# keyboard84.net
KiCad netlist of a schematic drawn in Altium Designer
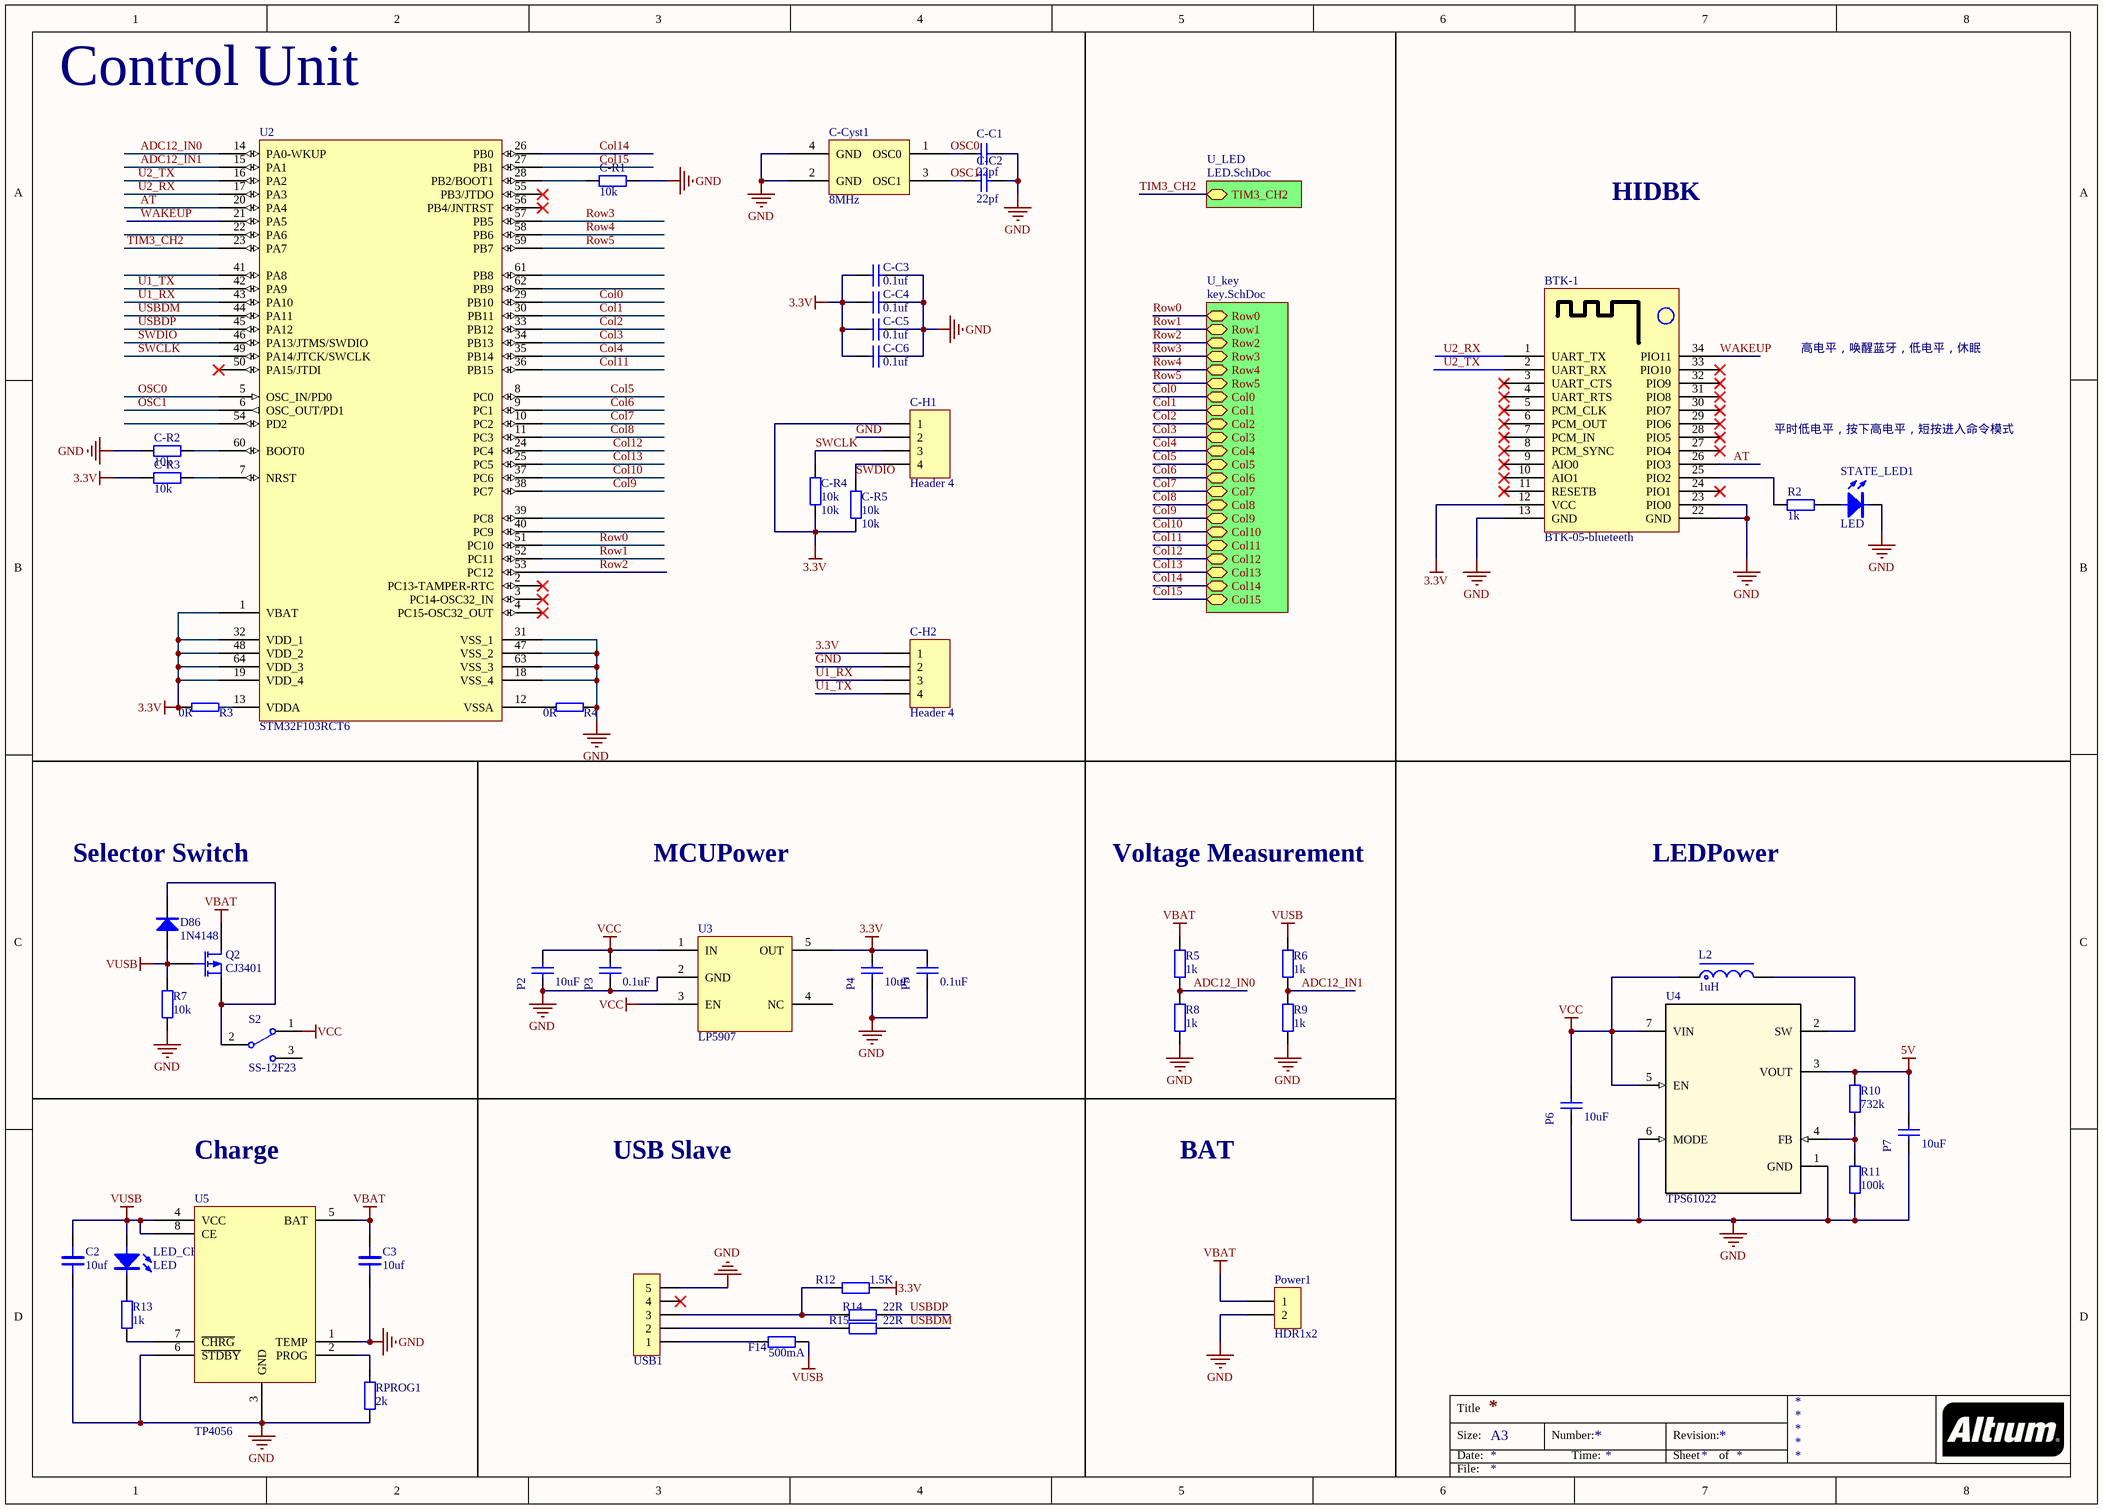
[diagram p0: keyboard84.SchDoc]

(export (version "E")
  (design (tool "Eeschema 10.0.6"))
  (components
    (comp (ref "BTK-1")
      (value "BTK-05-blueteeth")
      (footprint "BTK-05-bluteeth")
      (libsource (lib "MyLib") (part "BTK-05-blueteeth"))
    )
    (comp (ref "C-C1") (value "22pf") (footprint "C 0402_L") (libsource (lib "FJS") (part "Cap")))
    (comp (ref "C-C2") (value "22pf") (footprint "C 0402_L") (libsource (lib "FJS") (part "Cap")))
    (comp (ref "C-C3")
      (value "0.1uf")
      (footprint "C 0402_L")
      (description "Capacitor")
      (fields (field (name "PUBLISHER") "Altium Limited"))
      (libsource (lib "Miscellaneous Devices") (part "Cap"))
    )
    (comp (ref "C-C4")
      (value "0.1uf")
      (footprint "C 0402_L")
      (description "Capacitor")
      (fields (field (name "PUBLISHER") "Altium Limited"))
      (libsource (lib "Miscellaneous Devices") (part "Cap"))
    )
    (comp (ref "C-C5")
      (value "0.1uf")
      (footprint "C 0402_L")
      (description "Capacitor")
      (fields (field (name "PUBLISHER") "Altium Limited"))
      (libsource (lib "Miscellaneous Devices") (part "Cap"))
    )
    (comp (ref "C-C6")
      (value "0.1uf")
      (footprint "C 0402_L")
      (description "Capacitor")
      (fields (field (name "PUBLISHER") "Altium Limited"))
      (libsource (lib "Miscellaneous Devices") (part "Cap"))
    )
    (comp (ref "C-Cyst1") (value "8MHz") (footprint "OSC 3225-4P") (libsource (lib "FJS") (part "Crystal")))
    (comp (ref "C-H1")
      (value "Header 4")
      (footprint "GH1.25-4P - duplicate")
      (description "Header, 4-Pin")
      (fields (field (name "PUBLISHER") "Altium Limited"))
      (libsource (lib "Miscellaneous Connectors") (part "Header 4"))
    )
    (comp (ref "C-H2")
      (value "Header 4")
      (footprint "GH1.25-4P - duplicate")
      (description "Header, 4-Pin")
      (fields (field (name "PUBLISHER") "Altium Limited"))
      (libsource (lib "Miscellaneous Connectors") (part "Header 4"))
    )
    (comp (ref "C-R1")
      (value "10k")
      (footprint "R 0402_L")
      (description "Resistor")
      (fields (field (name "PUBLISHER") "Altium Limited"))
      (libsource (lib "") (part "Res2_4"))
    )
    (comp (ref "C-R2")
      (value "10k")
      (footprint "R 0402_L")
      (description "Resistor")
      (fields (field (name "PUBLISHER") "Altium Limited"))
      (libsource (lib "") (part "Res2_3"))
    )
    (comp (ref "C-R3")
      (value "10k")
      (footprint "R 0402_L")
      (description "Resistor")
      (fields (field (name "PUBLISHER") "Altium Limited"))
      (libsource (lib "") (part "Res2_3"))
    )
    (comp (ref "C-R4")
      (value "10k")
      (footprint "R 0402_L")
      (description "Resistor")
      (fields (field (name "ALTIUM_VALUE") "10k") (field (name "PUBLISHER") "Altium Limited"))
      (libsource (lib "") (part "Res2_1"))
    )
    (comp (ref "C-R5")
      (value "10k")
      (footprint "R 0402_L")
      (description "Resistor")
      (fields (field (name "ALTIUM_VALUE") "10k") (field (name "PUBLISHER") "Altium Limited"))
      (libsource (lib "") (part "Res2_1"))
    )
    (comp (ref "C2")
      (value "10uf")
      (footprint "C 0603_L")
      (description "Capacitor")
      (libsource (lib "General") (part "CAP"))
    )
    (comp (ref "C3")
      (value "10uf")
      (footprint "C 0603_L")
      (description "Capacitor")
      (libsource (lib "General") (part "CAP"))
    )
    (comp (ref "D86")
      (value "1N4148")
      (footprint "SOD-323")
      (description "开关二极管")
      (libsource (lib "0.2 -  二极管-整流桥") (part "1N4148"))
    )
    (comp (ref "F14")
      (value "500mA")
      (footprint "R 0603_L")
      (description "Resistor")
      (libsource (lib "Miscellaneous Devices") (part "Res2"))
    )
    (comp (ref "L2")
      (value "1uH")
      (footprint "CD31")
      (description "CD系列贴片线绕功率电感")
      (libsource (lib "0.1 - 电阻-电容-电感") (part "L-SMD"))
    )
    (comp (ref "LED_CHRG1") (value "LED") (footprint "LED 0603W") (libsource (lib "General") (part "LED")))
    (comp (ref "P2") (value "10uF") (footprint "C 0603_L") (libsource (lib "FJS") (part "Cap")))
    (comp (ref "P3") (value "0.1uF") (footprint "C 0603_L") (libsource (lib "FJS") (part "Cap")))
    (comp (ref "P4") (value "10uF") (footprint "C 0603_L") (libsource (lib "FJS") (part "Cap")))
    (comp (ref "P5") (value "0.1uF") (footprint "C 0603_L") (libsource (lib "FJS") (part "Cap")))
    (comp (ref "P6") (value "10uF") (footprint "C 0603_L") (libsource (lib "FJS") (part "Cap")))
    (comp (ref "P7") (value "10uF") (footprint "C 0603_L") (libsource (lib "FJS") (part "Cap")))
    (comp (ref "Power1")
      (value "HDR1x2")
      (footprint "HDR2.54-LI-2P")
      (description "Connector")
      (libsource (lib "General") (part "HDR1x2"))
    )
    (comp (ref "Q2")
      (value "CJ3401")
      (footprint "SOT23-3")
      (description "P-Channel MOSFET")
      (fields (field (name "PUBLISHER") "Altium Limited"))
      (libsource (lib "Fancy") (part "MOSFET-P"))
    )
    (comp (ref "R2")
      (value "1k")
      (footprint "R 0603_L")
      (description "Resistor")
      (libsource (lib "") (part "RES_1"))
    )
    (comp (ref "R3") (value "0R") (footprint "R 0402_L") (libsource (lib "ZIBO V2.0_Main") (part "R")))
    (comp (ref "R4") (value "0R") (footprint "R 0402_L") (libsource (lib "ZIBO V2.0_Main") (part "R")))
    (comp (ref "R5")
      (value "1k")
      (footprint "R 0603_L")
      (description "Resistor")
      (libsource (lib "General") (part "RES"))
    )
    (comp (ref "R6")
      (value "1k")
      (footprint "R 0603_L")
      (description "Resistor")
      (libsource (lib "General") (part "RES"))
    )
    (comp (ref "R7")
      (value "10k")
      (footprint "R 0603_L")
      (description "Resistor")
      (libsource (lib "General") (part "RES"))
    )
    (comp (ref "R8")
      (value "1k")
      (footprint "R 0603_L")
      (description "Resistor")
      (libsource (lib "General") (part "RES"))
    )
    (comp (ref "R9")
      (value "1k")
      (footprint "R 0603_L")
      (description "Resistor")
      (libsource (lib "General") (part "RES"))
    )
    (comp (ref "R10")
      (value "732k")
      (footprint "R 0603_L")
      (description "Resistor")
      (libsource (lib "General") (part "RES"))
    )
    (comp (ref "R11")
      (value "100k")
      (footprint "R 0603_L")
      (description "Resistor")
      (libsource (lib "General") (part "RES"))
    )
    (comp (ref "R12")
      (value "1.5K")
      (footprint "R 0402_L")
      (description "Resistor")
      (libsource (lib "") (part "Res2_2"))
    )
    (comp (ref "R13")
      (value "1k")
      (footprint "R 0603_L")
      (description "Resistor")
      (libsource (lib "General") (part "RES"))
    )
    (comp (ref "R14")
      (value "22R")
      (footprint "R 0402_L")
      (description "Resistor")
      (libsource (lib "") (part "Res2_2"))
    )
    (comp (ref "R15")
      (value "22R")
      (footprint "R 0402_L")
      (description "Resistor")
      (libsource (lib "") (part "Res2_2"))
    )
    (comp (ref "RPROG1")
      (value "2k")
      (footprint "R 0603_L")
      (description "Resistor")
      (libsource (lib "General") (part "RES"))
    )
    (comp (ref "S2")
      (value "SS-12F23")
      (footprint "SS-12D10")
      (description "1路波动开关")
      (fields (field (name "版权归属") "封装库来自淘宝 ID：黄晶宝石"))
      (libsource (lib "0.7 - 常用按键-开关") (part "SSW-1P"))
    )
    (comp (ref "STATE_LED1") (value "LED") (footprint "LED 0603W") (libsource (lib "General") (part "LED")))
    (comp (ref "U2")
      (value "STM32F103RCT6")
      (footprint "LQFP64_L")
      (description "MCU")
      (libsource (lib "General") (part "STM32F103RxTx"))
    )
    (comp (ref "U3") (value "LP5907") (footprint "SOT23-5N") (libsource (lib "Fancy") (part "LP5907MFX")))
    (comp (ref "U4") (value "TPS61022") (footprint "VQFN-7") (libsource (lib "Fancy") (part "TPS61022")))
    (comp (ref "U5") (value "TP4056") (footprint "ESOP8_N") (libsource (lib "MyLib") (part "TP4056")))
    (comp (ref "USB1")
      (value "USB Slave_c")
      (footprint "USB-MICRO - duplicate")
      (description "5P接插件")
      (libsource (lib "5.0 - 接插件-脚距1.25") (part "Header 5"))
    )
  )
  (nets
    (net (code "1") (name "/ADC12_IN0") (class "Default")
      (node (ref "R5") (pin "1") (pinfunction "1_1") (pintype "passive"))
      (node (ref "R8") (pin "2") (pinfunction "2_2") (pintype "passive"))
      (node (ref "U2") (pin "14") (pinfunction "PA0-WKUP_14") (pintype "bidirectional"))
    )
    (net (code "2") (name "/ADC12_IN1") (class "Default")
      (node (ref "R6") (pin "1") (pinfunction "1_1") (pintype "passive"))
      (node (ref "R9") (pin "2") (pinfunction "2_2") (pintype "passive"))
      (node (ref "U2") (pin "15") (pinfunction "PA1_15") (pintype "bidirectional"))
    )
    (net (code "3") (name "/AT") (class "Default")
      (node (ref "BTK-1") (pin "26") (pinfunction "PIO3_26") (pintype "passive"))
      (node (ref "U2") (pin "20") (pinfunction "PA4_20") (pintype "bidirectional"))
    )
    (net (code "4") (name "/Col0") (class "Default")
      (node (ref "U2") (pin "29") (pinfunction "PB10_29") (pintype "bidirectional"))
    )
    (net (code "5") (name "/Col1") (class "Default")
      (node (ref "U2") (pin "30") (pinfunction "PB11_30") (pintype "bidirectional"))
    )
    (net (code "6") (name "/Col2") (class "Default")
      (node (ref "U2") (pin "33") (pinfunction "PB12_33") (pintype "bidirectional"))
    )
    (net (code "7") (name "/Col3") (class "Default")
      (node (ref "U2") (pin "34") (pinfunction "PB13_34") (pintype "bidirectional"))
    )
    (net (code "8") (name "/Col4") (class "Default")
      (node (ref "U2") (pin "35") (pinfunction "PB14_35") (pintype "bidirectional"))
    )
    (net (code "9") (name "/Col5") (class "Default")
      (node (ref "U2") (pin "8") (pinfunction "PC0_8") (pintype "bidirectional"))
    )
    (net (code "10") (name "/Col6") (class "Default")
      (node (ref "U2") (pin "9") (pinfunction "PC1_9") (pintype "bidirectional"))
    )
    (net (code "11") (name "/Col7") (class "Default")
      (node (ref "U2") (pin "10") (pinfunction "PC2_10") (pintype "bidirectional"))
    )
    (net (code "12") (name "/Col8") (class "Default")
      (node (ref "U2") (pin "11") (pinfunction "PC3_11") (pintype "bidirectional"))
    )
    (net (code "13") (name "/Col9") (class "Default")
      (node (ref "U2") (pin "38") (pinfunction "PC7_38") (pintype "bidirectional"))
    )
    (net (code "14") (name "/Col10") (class "Default")
      (node (ref "U2") (pin "37") (pinfunction "PC6_37") (pintype "bidirectional"))
    )
    (net (code "15") (name "/Col11") (class "Default")
      (node (ref "U2") (pin "36") (pinfunction "PB15_36") (pintype "bidirectional"))
    )
    (net (code "16") (name "/Col12") (class "Default")
      (node (ref "U2") (pin "24") (pinfunction "PC4_24") (pintype "bidirectional"))
    )
    (net (code "17") (name "/Col13") (class "Default")
      (node (ref "U2") (pin "25") (pinfunction "PC5_25") (pintype "bidirectional"))
    )
    (net (code "18") (name "/Col14") (class "Default")
      (node (ref "U2") (pin "26") (pinfunction "PB0_26") (pintype "bidirectional"))
    )
    (net (code "19") (name "/Col15") (class "Default")
      (node (ref "U2") (pin "27") (pinfunction "PB1_27") (pintype "bidirectional"))
    )
    (net (code "20") (name "/OSC0") (class "Default")
      (node (ref "C-C1") (pin "2") (pinfunction "2_2") (pintype "passive"))
      (node (ref "C-Cyst1") (pin "1") (pinfunction "OSC0_1") (pintype "passive"))
      (node (ref "U2") (pin "5") (pinfunction "OSC_IN/PD0_5") (pintype "input"))
    )
    (net (code "21") (name "/OSC1") (class "Default")
      (node (ref "C-C2") (pin "2") (pinfunction "2_2") (pintype "passive"))
      (node (ref "C-Cyst1") (pin "3") (pinfunction "OSC1_3") (pintype "passive"))
      (node (ref "U2") (pin "6") (pinfunction "OSC_OUT/PD1_6") (pintype "output"))
    )
    (net (code "22") (name "/Row0") (class "Default")
      (node (ref "U2") (pin "51") (pinfunction "PC10_51") (pintype "bidirectional"))
    )
    (net (code "23") (name "/Row1") (class "Default")
      (node (ref "U2") (pin "52") (pinfunction "PC11_52") (pintype "bidirectional"))
    )
    (net (code "24") (name "/Row2") (class "Default")
      (node (ref "U2") (pin "53") (pinfunction "PC12_53") (pintype "bidirectional"))
    )
    (net (code "25") (name "/Row3") (class "Default")
      (node (ref "U2") (pin "57") (pinfunction "PB5_57") (pintype "bidirectional"))
    )
    (net (code "26") (name "/Row4") (class "Default")
      (node (ref "U2") (pin "58") (pinfunction "PB6_58") (pintype "bidirectional"))
    )
    (net (code "27") (name "/Row5") (class "Default")
      (node (ref "U2") (pin "59") (pinfunction "PB7_59") (pintype "bidirectional"))
    )
    (net (code "28") (name "/SWCLK") (class "Default")
      (node (ref "C-H1") (pin "3") (pinfunction "3_3") (pintype "passive"))
      (node (ref "C-R4") (pin "2") (pinfunction "2_2") (pintype "passive"))
      (node (ref "U2") (pin "49") (pinfunction "PA14/JTCK/SWCLK_49") (pintype "bidirectional"))
    )
    (net (code "29") (name "/SWDIO") (class "Default")
      (node (ref "C-H1") (pin "4") (pinfunction "4_4") (pintype "passive"))
      (node (ref "C-R5") (pin "2") (pinfunction "2_2") (pintype "passive"))
      (node (ref "U2") (pin "46") (pinfunction "PA13/JTMS/SWDIO_46") (pintype "bidirectional"))
    )
    (net (code "30") (name "/TIM3_CH2") (class "Default")
      (node (ref "U2") (pin "23") (pinfunction "PA7_23") (pintype "bidirectional"))
    )
    (net (code "31") (name "/U1_RX") (class "Default")
      (node (ref "C-H2") (pin "3") (pinfunction "3_3") (pintype "passive"))
      (node (ref "U2") (pin "43") (pinfunction "PA10_43") (pintype "bidirectional"))
    )
    (net (code "32") (name "/U1_TX") (class "Default")
      (node (ref "C-H2") (pin "4") (pinfunction "4_4") (pintype "passive"))
      (node (ref "U2") (pin "42") (pinfunction "PA9_42") (pintype "bidirectional"))
    )
    (net (code "33") (name "/U2_RX") (class "Default")
      (node (ref "BTK-1") (pin "1") (pinfunction "UART_TX_1") (pintype "passive"))
      (node (ref "U2") (pin "17") (pinfunction "PA3_17") (pintype "bidirectional"))
    )
    (net (code "34") (name "/U2_TX") (class "Default")
      (node (ref "BTK-1") (pin "2") (pinfunction "UART_RX_2") (pintype "passive"))
      (node (ref "U2") (pin "16") (pinfunction "PA2_16") (pintype "bidirectional"))
    )
    (net (code "35") (name "/USBDM") (class "Default")
      (node (ref "R15") (pin "1") (pinfunction "1_1") (pintype "passive"))
      (node (ref "U2") (pin "44") (pinfunction "PA11_44") (pintype "bidirectional"))
    )
    (net (code "36") (name "/USBDP") (class "Default")
      (node (ref "R14") (pin "1") (pinfunction "1_1") (pintype "passive"))
      (node (ref "U2") (pin "45") (pinfunction "PA12_45") (pintype "bidirectional"))
    )
    (net (code "37") (name "/WAKEUP") (class "Default")
      (node (ref "BTK-1") (pin "34") (pinfunction "PIO11_34") (pintype "passive"))
      (node (ref "U2") (pin "21") (pinfunction "PA5_21") (pintype "bidirectional"))
    )
    (net (code "38") (name "3.3V") (class "Default")
      (node (ref "BTK-1") (pin "12") (pinfunction "VCC_12") (pintype "passive"))
      (node (ref "C-C3") (pin "2") (pinfunction "2_2") (pintype "passive"))
      (node (ref "C-C4") (pin "2") (pinfunction "2_2") (pintype "passive"))
      (node (ref "C-C5") (pin "2") (pinfunction "2_2") (pintype "passive"))
      (node (ref "C-C6") (pin "2") (pinfunction "2_2") (pintype "passive"))
      (node (ref "C-H1") (pin "1") (pinfunction "1_1") (pintype "passive"))
      (node (ref "C-H2") (pin "1") (pinfunction "1_1") (pintype "passive"))
      (node (ref "C-R3") (pin "1") (pinfunction "1_1") (pintype "passive"))
      (node (ref "C-R4") (pin "1") (pinfunction "1_1") (pintype "passive"))
      (node (ref "C-R5") (pin "1") (pinfunction "1_1") (pintype "passive"))
      (node (ref "P4") (pin "2") (pinfunction "2_2") (pintype "passive"))
      (node (ref "P5") (pin "2") (pinfunction "2_2") (pintype "passive"))
      (node (ref "R12") (pin "1") (pinfunction "1_1") (pintype "passive"))
      (node (ref "R3") (pin "2") (pinfunction "2_2") (pintype "passive"))
      (node (ref "U2") (pin "1") (pinfunction "VBAT_1") (pintype "power_in"))
      (node (ref "U2") (pin "19") (pinfunction "VDD_4_19") (pintype "power_in"))
      (node (ref "U2") (pin "32") (pinfunction "VDD_1_32") (pintype "power_in"))
      (node (ref "U2") (pin "48") (pinfunction "VDD_2_48") (pintype "power_in"))
      (node (ref "U2") (pin "64") (pinfunction "VDD_3_64") (pintype "power_in"))
      (node (ref "U3") (pin "5") (pinfunction "OUT_5") (pintype "passive"))
    )
    (net (code "39") (name "5V") (class "Default")
      (node (ref "P7") (pin "2") (pinfunction "2_2") (pintype "passive"))
      (node (ref "R10") (pin "2") (pinfunction "2_2") (pintype "passive"))
      (node (ref "U4") (pin "3") (pinfunction "VOUT_3") (pintype "power_in"))
    )
    (net (code "40") (name "GND") (class "Default")
      (node (ref "BTK-1") (pin "13") (pinfunction "GND_13") (pintype "passive"))
      (node (ref "BTK-1") (pin "22") (pinfunction "GND_22") (pintype "passive"))
      (node (ref "BTK-1") (pin "23") (pinfunction "PIO0_23") (pintype "passive"))
      (node (ref "C-C1") (pin "1") (pinfunction "1_1") (pintype "passive"))
      (node (ref "C-C2") (pin "1") (pinfunction "1_1") (pintype "passive"))
      (node (ref "C-C3") (pin "1") (pinfunction "1_1") (pintype "passive"))
      (node (ref "C-C4") (pin "1") (pinfunction "1_1") (pintype "passive"))
      (node (ref "C-C5") (pin "1") (pinfunction "1_1") (pintype "passive"))
      (node (ref "C-C6") (pin "1") (pinfunction "1_1") (pintype "passive"))
      (node (ref "C-Cyst1") (pin "2") (pinfunction "GND_2") (pintype "passive"))
      (node (ref "C-Cyst1") (pin "4") (pinfunction "GND_4") (pintype "passive"))
      (node (ref "C-H1") (pin "2") (pinfunction "2_2") (pintype "passive"))
      (node (ref "C-H2") (pin "2") (pinfunction "2_2") (pintype "passive"))
      (node (ref "C-R1") (pin "1") (pinfunction "1_1") (pintype "passive"))
      (node (ref "C-R2") (pin "1") (pinfunction "1_1") (pintype "passive"))
      (node (ref "C2") (pin "1") (pinfunction "1_1") (pintype "passive"))
      (node (ref "C3") (pin "1") (pinfunction "1_1") (pintype "passive"))
      (node (ref "P2") (pin "1") (pinfunction "1_1") (pintype "passive"))
      (node (ref "P3") (pin "1") (pinfunction "1_1") (pintype "passive"))
      (node (ref "P4") (pin "1") (pinfunction "1_1") (pintype "passive"))
      (node (ref "P5") (pin "1") (pinfunction "1_1") (pintype "passive"))
      (node (ref "P6") (pin "1") (pinfunction "1_1") (pintype "passive"))
      (node (ref "P7") (pin "1") (pinfunction "1_1") (pintype "passive"))
      (node (ref "Power1") (pin "2") (pinfunction "2_2") (pintype "passive"))
      (node (ref "R11") (pin "1") (pinfunction "1_1") (pintype "passive"))
      (node (ref "R4") (pin "1") (pinfunction "1_1") (pintype "passive"))
      (node (ref "R7") (pin "1") (pinfunction "1_1") (pintype "passive"))
      (node (ref "R8") (pin "1") (pinfunction "1_1") (pintype "passive"))
      (node (ref "R9") (pin "1") (pinfunction "1_1") (pintype "passive"))
      (node (ref "RPROG1") (pin "1") (pinfunction "1_1") (pintype "passive"))
      (node (ref "STATE_LED1") (pin "2") (pinfunction "C_2") (pintype "passive"))
      (node (ref "U2") (pin "18") (pinfunction "VSS_4_18") (pintype "power_in"))
      (node (ref "U2") (pin "31") (pinfunction "VSS_1_31") (pintype "power_in"))
      (node (ref "U2") (pin "47") (pinfunction "VSS_2_47") (pintype "power_in"))
      (node (ref "U2") (pin "63") (pinfunction "VSS_3_63") (pintype "power_in"))
      (node (ref "U3") (pin "2") (pinfunction "GND_2") (pintype "passive"))
      (node (ref "U4") (pin "1") (pinfunction "GND_1") (pintype "power_in"))
      (node (ref "U4") (pin "6") (pinfunction "MODE_6") (pintype "input"))
      (node (ref "U5") (pin "1") (pinfunction "TEMP_1") (pintype "passive"))
      (node (ref "U5") (pin "3") (pinfunction "GND_3") (pintype "passive"))
      (node (ref "U5") (pin "6") (pinfunction "~{STDBY}_6") (pintype "passive"))
      (node (ref "USB1") (pin "5") (pinfunction "5_5") (pintype "passive"))
    )
    (net (code "41") (name "Net-(BTK-1-PIO2)") (class "Default")
      (node (ref "BTK-1") (pin "25") (pinfunction "PIO2_25") (pintype "passive"))
      (node (ref "R2") (pin "1") (pinfunction "1_1") (pintype "passive"))
    )
    (net (code "42") (name "Net-(D86-K)") (class "Default")
      (node (ref "D86") (pin "2") (pinfunction "K_2") (pintype "passive"))
      (node (ref "Q2") (pin "3") (pinfunction "S_3") (pintype "passive"))
      (node (ref "S2") (pin "2") (pinfunction "2_2") (pintype "passive"))
    )
    (net (code "43") (name "Net-(F14-Pad2)") (class "Default")
      (node (ref "F14") (pin "2") (pinfunction "2_2") (pintype "passive"))
      (node (ref "USB1") (pin "1") (pinfunction "1_1") (pintype "passive"))
    )
    (net (code "44") (name "Net-(LED_CHRG1-C)") (class "Default")
      (node (ref "LED_CHRG1") (pin "2") (pinfunction "C_2") (pintype "passive"))
      (node (ref "R13") (pin "2") (pinfunction "2_2") (pintype "passive"))
    )
    (net (code "45") (name "Net-(R12-Pad2)") (class "Default")
      (node (ref "R12") (pin "2") (pinfunction "2_2") (pintype "passive"))
      (node (ref "R14") (pin "2") (pinfunction "2_2") (pintype "passive"))
      (node (ref "USB1") (pin "3") (pinfunction "3_3") (pintype "passive"))
    )
    (net (code "46") (name "Net-(R15-Pad2)") (class "Default")
      (node (ref "R15") (pin "2") (pinfunction "2_2") (pintype "passive"))
      (node (ref "USB1") (pin "2") (pinfunction "2_2") (pintype "passive"))
    )
    (net (code "47") (name "Net-(STATE_LED1-A)") (class "Default")
      (node (ref "R2") (pin "2") (pinfunction "2_2") (pintype "passive"))
      (node (ref "STATE_LED1") (pin "1") (pinfunction "A_1") (pintype "passive"))
    )
    (net (code "48") (name "Net-(U2-BOOT0)") (class "Default")
      (node (ref "C-R2") (pin "2") (pinfunction "2_2") (pintype "passive"))
      (node (ref "U2") (pin "60") (pinfunction "BOOT0_60") (pintype "bidirectional"))
    )
    (net (code "49") (name "Net-(U2-NRST)") (class "Default")
      (node (ref "C-R3") (pin "2") (pinfunction "2_2") (pintype "passive"))
      (node (ref "U2") (pin "7") (pinfunction "NRST_7") (pintype "bidirectional"))
    )
    (net (code "50") (name "Net-(U2-PB2{slash}BOOT1)") (class "Default")
      (node (ref "C-R1") (pin "2") (pinfunction "2_2") (pintype "passive"))
      (node (ref "U2") (pin "28") (pinfunction "PB2/BOOT1_28") (pintype "bidirectional"))
    )
    (net (code "51") (name "Net-(U2-VDDA)") (class "Default")
      (node (ref "R3") (pin "1") (pinfunction "1_1") (pintype "passive"))
      (node (ref "U2") (pin "13") (pinfunction "VDDA_13") (pintype "power_in"))
    )
    (net (code "52") (name "Net-(U2-VSSA)") (class "Default")
      (node (ref "R4") (pin "2") (pinfunction "2_2") (pintype "passive"))
      (node (ref "U2") (pin "12") (pinfunction "VSSA_12") (pintype "power_in"))
    )
    (net (code "53") (name "Net-(U4-FB)") (class "Default")
      (node (ref "R10") (pin "1") (pinfunction "1_1") (pintype "passive"))
      (node (ref "R11") (pin "2") (pinfunction "2_2") (pintype "passive"))
      (node (ref "U4") (pin "4") (pinfunction "FB_4") (pintype "input"))
    )
    (net (code "54") (name "Net-(U4-SW)") (class "Default")
      (node (ref "L2") (pin "2") (pinfunction "2_2") (pintype "passive"))
      (node (ref "U4") (pin "2") (pinfunction "SW_2") (pintype "power_in"))
    )
    (net (code "55") (name "Net-(U5-PROG)") (class "Default")
      (node (ref "RPROG1") (pin "2") (pinfunction "2_2") (pintype "passive"))
      (node (ref "U5") (pin "2") (pinfunction "PROG_2") (pintype "passive"))
    )
    (net (code "56") (name "Net-(U5-~{CHRG})") (class "Default")
      (node (ref "R13") (pin "1") (pinfunction "1_1") (pintype "passive"))
      (node (ref "U5") (pin "7") (pinfunction "~{CHRG}_7") (pintype "passive"))
    )
    (net (code "57") (name "VBAT") (class "Default")
      (node (ref "C3") (pin "2") (pinfunction "2_2") (pintype "passive"))
      (node (ref "Power1") (pin "1") (pinfunction "1_1") (pintype "passive"))
      (node (ref "Q2") (pin "2") (pinfunction "D_2") (pintype "passive"))
      (node (ref "R5") (pin "2") (pinfunction "2_2") (pintype "passive"))
      (node (ref "U5") (pin "5") (pinfunction "BAT_5") (pintype "passive"))
    )
    (net (code "58") (name "VCC") (class "Default")
      (node (ref "L2") (pin "1") (pinfunction "1_1") (pintype "passive"))
      (node (ref "P2") (pin "2") (pinfunction "2_2") (pintype "passive"))
      (node (ref "P3") (pin "2") (pinfunction "2_2") (pintype "passive"))
      (node (ref "P6") (pin "2") (pinfunction "2_2") (pintype "passive"))
      (node (ref "S2") (pin "1") (pinfunction "1_1") (pintype "passive"))
      (node (ref "U3") (pin "1") (pinfunction "IN_1") (pintype "passive"))
      (node (ref "U3") (pin "3") (pinfunction "EN_3") (pintype "passive"))
      (node (ref "U4") (pin "5") (pinfunction "EN_5") (pintype "input"))
      (node (ref "U4") (pin "7") (pinfunction "VIN_7") (pintype "power_in"))
    )
    (net (code "59") (name "VUSB") (class "Default")
      (node (ref "C2") (pin "2") (pinfunction "2_2") (pintype "passive"))
      (node (ref "D86") (pin "1") (pinfunction "A_1") (pintype "passive"))
      (node (ref "F14") (pin "1") (pinfunction "1_1") (pintype "passive"))
      (node (ref "LED_CHRG1") (pin "1") (pinfunction "A_1") (pintype "passive"))
      (node (ref "Q2") (pin "1") (pinfunction "G_1") (pintype "passive"))
      (node (ref "R6") (pin "2") (pinfunction "2_2") (pintype "passive"))
      (node (ref "R7") (pin "2") (pinfunction "2_2") (pintype "passive"))
      (node (ref "U5") (pin "4") (pinfunction "VCC_4") (pintype "passive"))
      (node (ref "U5") (pin "8") (pinfunction "CE_8") (pintype "passive"))
    )
    (net (code "60") (name "unconnected-(BTK-1-AIO0-Pad9)") (class "Default")
      (node (ref "BTK-1") (pin "9") (pinfunction "AIO0_9") (pintype "passive+no_connect"))
    )
    (net (code "61") (name "unconnected-(BTK-1-AIO1-Pad10)") (class "Default")
      (node (ref "BTK-1") (pin "10") (pinfunction "AIO1_10") (pintype "passive+no_connect"))
    )
    (net (code "62") (name "unconnected-(BTK-1-PCM_CLK-Pad5)") (class "Default")
      (node (ref "BTK-1") (pin "5") (pinfunction "PCM_CLK_5") (pintype "passive+no_connect"))
    )
    (net (code "63") (name "unconnected-(BTK-1-PCM_IN-Pad7)") (class "Default")
      (node (ref "BTK-1") (pin "7") (pinfunction "PCM_IN_7") (pintype "passive+no_connect"))
    )
    (net (code "64") (name "unconnected-(BTK-1-PCM_OUT-Pad6)") (class "Default")
      (node (ref "BTK-1") (pin "6") (pinfunction "PCM_OUT_6") (pintype "passive+no_connect"))
    )
    (net (code "65") (name "unconnected-(BTK-1-PCM_SYNC-Pad8)") (class "Default")
      (node (ref "BTK-1") (pin "8") (pinfunction "PCM_SYNC_8") (pintype "passive+no_connect"))
    )
    (net (code "66") (name "unconnected-(BTK-1-PIO1-Pad24)") (class "Default")
      (node (ref "BTK-1") (pin "24") (pinfunction "PIO1_24") (pintype "passive+no_connect"))
    )
    (net (code "67") (name "unconnected-(BTK-1-PIO4-Pad27)") (class "Default")
      (node (ref "BTK-1") (pin "27") (pinfunction "PIO4_27") (pintype "passive+no_connect"))
    )
    (net (code "68") (name "unconnected-(BTK-1-PIO5-Pad28)") (class "Default")
      (node (ref "BTK-1") (pin "28") (pinfunction "PIO5_28") (pintype "passive+no_connect"))
    )
    (net (code "69") (name "unconnected-(BTK-1-PIO6-Pad29)") (class "Default")
      (node (ref "BTK-1") (pin "29") (pinfunction "PIO6_29") (pintype "passive+no_connect"))
    )
    (net (code "70") (name "unconnected-(BTK-1-PIO7-Pad30)") (class "Default")
      (node (ref "BTK-1") (pin "30") (pinfunction "PIO7_30") (pintype "passive+no_connect"))
    )
    (net (code "71") (name "unconnected-(BTK-1-PIO8-Pad31)") (class "Default")
      (node (ref "BTK-1") (pin "31") (pinfunction "PIO8_31") (pintype "passive+no_connect"))
    )
    (net (code "72") (name "unconnected-(BTK-1-PIO9-Pad32)") (class "Default")
      (node (ref "BTK-1") (pin "32") (pinfunction "PIO9_32") (pintype "passive+no_connect"))
    )
    (net (code "73") (name "unconnected-(BTK-1-PIO10-Pad33)") (class "Default")
      (node (ref "BTK-1") (pin "33") (pinfunction "PIO10_33") (pintype "passive+no_connect"))
    )
    (net (code "74") (name "unconnected-(BTK-1-RESETB-Pad11)") (class "Default")
      (node (ref "BTK-1") (pin "11") (pinfunction "RESETB_11") (pintype "passive+no_connect"))
    )
    (net (code "75") (name "unconnected-(BTK-1-UART_CTS-Pad3)") (class "Default")
      (node (ref "BTK-1") (pin "3") (pinfunction "UART_CTS_3") (pintype "passive+no_connect"))
    )
    (net (code "76") (name "unconnected-(BTK-1-UART_RTS-Pad4)") (class "Default")
      (node (ref "BTK-1") (pin "4") (pinfunction "UART_RTS_4") (pintype "passive+no_connect"))
    )
    (net (code "77") (name "unconnected-(S2-Pad3)") (class "Default")
      (node (ref "S2") (pin "3") (pinfunction "3_3") (pintype "passive"))
    )
    (net (code "78") (name "unconnected-(U2-PA6-Pad22)") (class "Default")
      (node (ref "U2") (pin "22") (pinfunction "PA6_22") (pintype "bidirectional"))
    )
    (net (code "79") (name "unconnected-(U2-PA8-Pad41)") (class "Default")
      (node (ref "U2") (pin "41") (pinfunction "PA8_41") (pintype "bidirectional"))
    )
    (net (code "80") (name "unconnected-(U2-PA15{slash}JTDI-Pad50)") (class "Default")
      (node (ref "U2") (pin "50") (pinfunction "PA15/JTDI_50") (pintype "bidirectional+no_connect"))
    )
    (net (code "81") (name "unconnected-(U2-PB3{slash}JTDO-Pad55)") (class "Default")
      (node (ref "U2") (pin "55") (pinfunction "PB3/JTDO_55") (pintype "bidirectional+no_connect"))
    )
    (net (code "82") (name "unconnected-(U2-PB4{slash}JNTRST-Pad56)") (class "Default")
      (node (ref "U2") (pin "56") (pinfunction "PB4/JNTRST_56") (pintype "bidirectional+no_connect"))
    )
    (net (code "83") (name "unconnected-(U2-PB8-Pad61)") (class "Default")
      (node (ref "U2") (pin "61") (pinfunction "PB8_61") (pintype "bidirectional"))
    )
    (net (code "84") (name "unconnected-(U2-PB9-Pad62)") (class "Default")
      (node (ref "U2") (pin "62") (pinfunction "PB9_62") (pintype "bidirectional"))
    )
    (net (code "85") (name "unconnected-(U2-PC8-Pad39)") (class "Default")
      (node (ref "U2") (pin "39") (pinfunction "PC8_39") (pintype "bidirectional"))
    )
    (net (code "86") (name "unconnected-(U2-PC9-Pad40)") (class "Default")
      (node (ref "U2") (pin "40") (pinfunction "PC9_40") (pintype "bidirectional"))
    )
    (net (code "87") (name "unconnected-(U2-PC13-TAMPER-RTC-Pad2)") (class "Default")
      (node (ref "U2") (pin "2") (pinfunction "PC13-TAMPER-RTC_2") (pintype "bidirectional+no_connect"))
    )
    (net (code "88") (name "unconnected-(U2-PC14-OSC32_IN-Pad3)") (class "Default")
      (node (ref "U2") (pin "3") (pinfunction "PC14-OSC32_IN_3") (pintype "bidirectional+no_connect"))
    )
    (net (code "89") (name "unconnected-(U2-PC15-OSC32_OUT-Pad4)") (class "Default")
      (node (ref "U2") (pin "4") (pinfunction "PC15-OSC32_OUT_4") (pintype "bidirectional+no_connect"))
    )
    (net (code "90") (name "unconnected-(U2-PD2-Pad54)") (class "Default")
      (node (ref "U2") (pin "54") (pinfunction "PD2_54") (pintype "bidirectional"))
    )
    (net (code "91") (name "unconnected-(U3-NC-Pad4)") (class "Default")
      (node (ref "U3") (pin "4") (pinfunction "NC_4") (pintype "passive"))
    )
    (net (code "92") (name "unconnected-(USB1-Pad4)") (class "Default")
      (node (ref "USB1") (pin "4") (pinfunction "4_4") (pintype "passive+no_connect"))
    )
  )
)
